# Nusbio1_0_Light.net
KiCad netlist of a schematic drawn in EAGLE
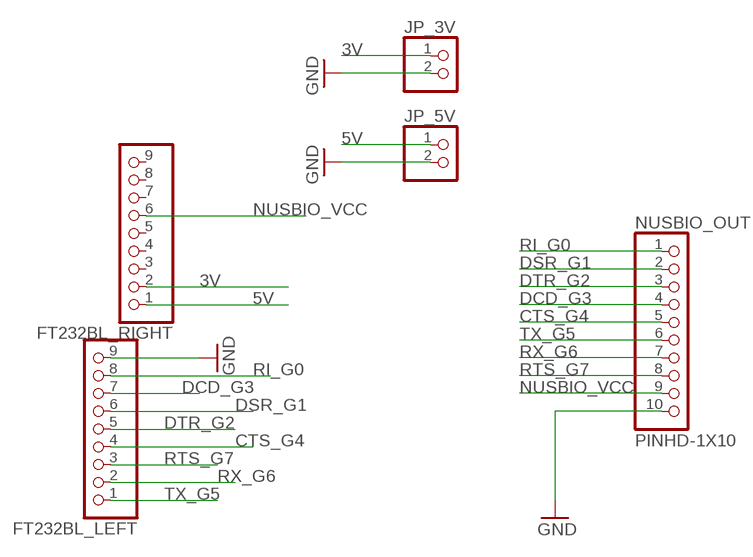
[diagram p0: schematic, sheet 1]

(export (version "E")
  (design (tool "Eeschema 10.0.6"))
  (components
    (comp (ref "FT232BL_LEFT")
      (value "PINHD-1X9")
      (footprint "eagle-import:1X09-BIG")
      (libsource (lib "eagle-import") (part "PINHD-1X9"))
    )
    (comp (ref "FT232BL_RIGHT")
      (value "PINHD-1X9")
      (footprint "eagle-import:1X09-BIG")
      (libsource (lib "eagle-import") (part "PINHD-1X9"))
    )
    (comp (ref "JP_3V")
      (value "PINHD-1X2")
      (footprint "eagle-import:1X02")
      (libsource (lib "eagle-import") (part "PINHD-1X2"))
    )
    (comp (ref "JP_5V")
      (value "PINHD-1X2")
      (footprint "eagle-import:1X02")
      (libsource (lib "eagle-import") (part "PINHD-1X2"))
    )
    (comp (ref "NUSBIO_OUT")
      (value "PINHD-1X10")
      (footprint "eagle-import:1X10-BIG")
      (libsource (lib "eagle-import") (part "PINHD-1X10"))
    )
  )
  (nets
    (net (code "1") (name "/3V") (class "Default")
      (node (ref "FT232BL_RIGHT") (pin "2") (pinfunction "2_2") (pintype "passive"))
      (node (ref "JP_3V") (pin "1") (pinfunction "1_1") (pintype "passive"))
    )
    (net (code "2") (name "/5V") (class "Default")
      (node (ref "FT232BL_RIGHT") (pin "1") (pinfunction "1_1") (pintype "passive"))
      (node (ref "JP_5V") (pin "1") (pinfunction "1_1") (pintype "passive"))
    )
    (net (code "3") (name "/CTS_G4") (class "Default")
      (node (ref "FT232BL_LEFT") (pin "4") (pinfunction "4_4") (pintype "passive"))
      (node (ref "NUSBIO_OUT") (pin "5") (pinfunction "5_5") (pintype "passive"))
    )
    (net (code "4") (name "/DCD_G3") (class "Default")
      (node (ref "FT232BL_LEFT") (pin "7") (pinfunction "7_7") (pintype "passive"))
      (node (ref "NUSBIO_OUT") (pin "4") (pinfunction "4_4") (pintype "passive"))
    )
    (net (code "5") (name "/DSR_G1") (class "Default")
      (node (ref "FT232BL_LEFT") (pin "6") (pinfunction "6_6") (pintype "passive"))
      (node (ref "NUSBIO_OUT") (pin "2") (pinfunction "2_2") (pintype "passive"))
    )
    (net (code "6") (name "/DTR_G2") (class "Default")
      (node (ref "FT232BL_LEFT") (pin "5") (pinfunction "5_5") (pintype "passive"))
      (node (ref "NUSBIO_OUT") (pin "3") (pinfunction "3_3") (pintype "passive"))
    )
    (net (code "7") (name "/NUSBIO_VCC") (class "Default")
      (node (ref "FT232BL_RIGHT") (pin "6") (pinfunction "6_6") (pintype "passive"))
      (node (ref "NUSBIO_OUT") (pin "9") (pinfunction "9_9") (pintype "passive"))
    )
    (net (code "8") (name "/RI_G0") (class "Default")
      (node (ref "FT232BL_LEFT") (pin "8") (pinfunction "8_8") (pintype "passive"))
      (node (ref "NUSBIO_OUT") (pin "1") (pinfunction "1_1") (pintype "passive"))
    )
    (net (code "9") (name "/RTS_G7") (class "Default")
      (node (ref "FT232BL_LEFT") (pin "3") (pinfunction "3_3") (pintype "passive"))
      (node (ref "NUSBIO_OUT") (pin "8") (pinfunction "8_8") (pintype "passive"))
    )
    (net (code "10") (name "/RX_G6") (class "Default")
      (node (ref "FT232BL_LEFT") (pin "2") (pinfunction "2_2") (pintype "passive"))
      (node (ref "NUSBIO_OUT") (pin "7") (pinfunction "7_7") (pintype "passive"))
    )
    (net (code "11") (name "/TX_G5") (class "Default")
      (node (ref "FT232BL_LEFT") (pin "1") (pinfunction "1_1") (pintype "passive"))
      (node (ref "NUSBIO_OUT") (pin "6") (pinfunction "6_6") (pintype "passive"))
    )
    (net (code "12") (name "GND") (class "Default")
      (node (ref "FT232BL_LEFT") (pin "9") (pinfunction "9_9") (pintype "passive"))
      (node (ref "JP_3V") (pin "2") (pinfunction "2_2") (pintype "passive"))
      (node (ref "JP_5V") (pin "2") (pinfunction "2_2") (pintype "passive"))
      (node (ref "NUSBIO_OUT") (pin "10") (pinfunction "10_10") (pintype "passive"))
    )
    (net (code "13") (name "unconnected-(FT232BL_RIGHT-Pad3)") (class "Default")
      (node (ref "FT232BL_RIGHT") (pin "3") (pinfunction "3_3") (pintype "passive"))
    )
    (net (code "14") (name "unconnected-(FT232BL_RIGHT-Pad4)") (class "Default")
      (node (ref "FT232BL_RIGHT") (pin "4") (pinfunction "4_4") (pintype "passive"))
    )
    (net (code "15") (name "unconnected-(FT232BL_RIGHT-Pad5)") (class "Default")
      (node (ref "FT232BL_RIGHT") (pin "5") (pinfunction "5_5") (pintype "passive"))
    )
    (net (code "16") (name "unconnected-(FT232BL_RIGHT-Pad7)") (class "Default")
      (node (ref "FT232BL_RIGHT") (pin "7") (pinfunction "7_7") (pintype "passive"))
    )
    (net (code "17") (name "unconnected-(FT232BL_RIGHT-Pad8)") (class "Default")
      (node (ref "FT232BL_RIGHT") (pin "8") (pinfunction "8_8") (pintype "passive"))
    )
    (net (code "18") (name "unconnected-(FT232BL_RIGHT-Pad9)") (class "Default")
      (node (ref "FT232BL_RIGHT") (pin "9") (pinfunction "9_9") (pintype "passive"))
    )
  )
)
